# POWER.net
KiCad netlist of a schematic drawn in Altium Designer
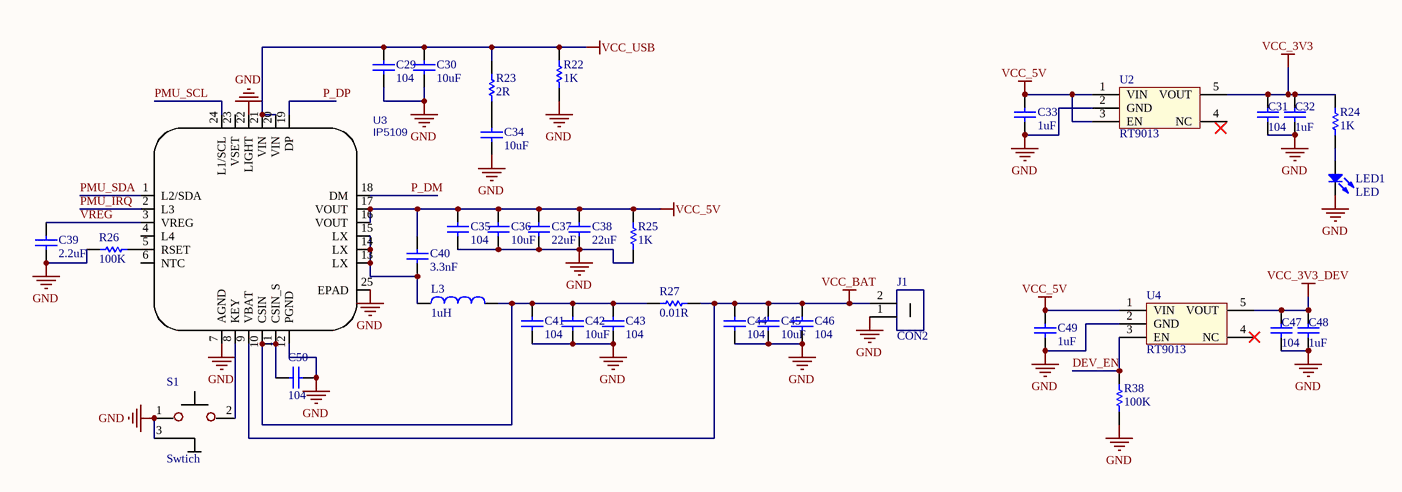
[diagram p0: POWER.SchDoc]

(export (version "E")
  (design (tool "Eeschema 10.0.6"))
  (components
    (comp (ref "C29")
      (value "104")
      (footprint "C 0603")
      (description "Capacitor")
      (libsource (lib "Miscellaneous Devices") (part "Cap"))
    )
    (comp (ref "C30")
      (value "10uF")
      (footprint "C 0603")
      (description "Capacitor")
      (libsource (lib "Miscellaneous Devices") (part "Cap"))
    )
    (comp (ref "C31") (value "104") (footprint "C 0603") (libsource (lib "Sheet") (part "CAP")))
    (comp (ref "C32") (value "1uF") (footprint "C 0603") (libsource (lib "Sheet") (part "CAP")))
    (comp (ref "C33") (value "1uF") (footprint "C 0603") (libsource (lib "Sheet") (part "CAP")))
    (comp (ref "C34")
      (value "10uF")
      (footprint "C 0603")
      (description "Capacitor")
      (libsource (lib "Miscellaneous Devices") (part "Cap"))
    )
    (comp (ref "C35")
      (value "104")
      (footprint "C 0603")
      (description "Capacitor")
      (libsource (lib "Miscellaneous Devices") (part "Cap"))
    )
    (comp (ref "C36")
      (value "10uF")
      (footprint "C 0603")
      (description "Capacitor")
      (libsource (lib "Miscellaneous Devices") (part "Cap"))
    )
    (comp (ref "C37")
      (value "22uF")
      (footprint "C 0603")
      (description "Capacitor")
      (libsource (lib "Miscellaneous Devices") (part "Cap"))
    )
    (comp (ref "C38")
      (value "22uF")
      (footprint "C 0603")
      (description "Capacitor")
      (libsource (lib "Miscellaneous Devices") (part "Cap"))
    )
    (comp (ref "C39") (value "2.2uF") (footprint "C 0603") (libsource (lib "Sheet") (part "CAP")))
    (comp (ref "C40")
      (value "3.3nF")
      (footprint "C 0603")
      (description "Capacitor")
      (libsource (lib "Miscellaneous Devices") (part "Cap"))
    )
    (comp (ref "C41")
      (value "104")
      (footprint "C 0603")
      (description "Capacitor")
      (libsource (lib "Miscellaneous Devices") (part "Cap"))
    )
    (comp (ref "C42")
      (value "10uF")
      (footprint "C 0603")
      (description "Capacitor")
      (libsource (lib "Miscellaneous Devices") (part "Cap"))
    )
    (comp (ref "C43")
      (value "104")
      (footprint "C 0603")
      (description "Capacitor")
      (libsource (lib "Miscellaneous Devices") (part "Cap"))
    )
    (comp (ref "C44")
      (value "104")
      (footprint "C 0603")
      (description "Capacitor")
      (libsource (lib "Miscellaneous Devices") (part "Cap"))
    )
    (comp (ref "C45")
      (value "10uF")
      (footprint "C 0603")
      (description "Capacitor")
      (libsource (lib "Miscellaneous Devices") (part "Cap"))
    )
    (comp (ref "C46")
      (value "104")
      (footprint "C 0603")
      (description "Capacitor")
      (libsource (lib "Miscellaneous Devices") (part "Cap"))
    )
    (comp (ref "C47") (value "104") (footprint "C 0603") (libsource (lib "Sheet") (part "CAP")))
    (comp (ref "C48") (value "1uF") (footprint "C 0603") (libsource (lib "Sheet") (part "CAP")))
    (comp (ref "C49") (value "1uF") (footprint "C 0603") (libsource (lib "Sheet") (part "CAP")))
    (comp (ref "C50")
      (value "104")
      (footprint "C 0603")
      (description "Capacitor")
      (libsource (lib "Miscellaneous Devices") (part "Cap"))
    )
    (comp (ref "J1") (value "CON2") (footprint "XH-2P-SMD") (libsource (lib "Sheet") (part "CON2")))
    (comp (ref "L3")
      (value "1uH")
      (footprint "L_7*7")
      (description "Inductor")
      (libsource (lib "Miscellaneous Devices") (part "Inductor"))
    )
    (comp (ref "LED1") (value "LED") (footprint "0603_LED") (libsource (lib "squ-guiboard") (part "LED")))
    (comp (ref "R22") (value "1K") (footprint "R 0603") (libsource (lib "Sheet") (part "RES")))
    (comp (ref "R23") (value "2R") (footprint "R 0603") (libsource (lib "Sheet") (part "RES")))
    (comp (ref "R24") (value "1K") (footprint "R 0603") (libsource (lib "Sheet") (part "RES")))
    (comp (ref "R25") (value "1K") (footprint "R 0603") (libsource (lib "Sheet") (part "RES")))
    (comp (ref "R26") (value "100K") (footprint "R 0603") (libsource (lib "Sheet") (part "RES")))
    (comp (ref "R27") (value "0.01R") (footprint "R 1206") (libsource (lib "Sheet") (part "RES")))
    (comp (ref "R38") (value "100K") (footprint "R 0603") (libsource (lib "Sheet") (part "RES")))
    (comp (ref "S1") (value "Swtich") (footprint "SW3*6") (libsource (lib "Sheet") (part "Switch-th")))
    (comp (ref "U2")
      (value "RT9013")
      (footprint "SOT23-5")
      (description "500mA低压差LDO")
      (libsource (lib "squ-guiboard") (part "RT9013"))
    )
    (comp (ref "U3")
      (value "IP5109")
      (footprint "QFN-24")
      (fields (field (name "BOM_SUPPLIER PART") "C181699") (field (name "CONTRIBUTOR") "LCSC"))
      (libsource (lib "Sheet") (part "IP5109"))
    )
    (comp (ref "U4")
      (value "RT9013")
      (footprint "SOT23-5")
      (description "500mA低压差LDO")
      (libsource (lib "squ-guiboard") (part "RT9013"))
    )
  )
  (nets
    (net (code "1") (name "/DEV_EN") (class "Default")
      (node (ref "R38") (pin "2") (pinfunction "2_2") (pintype "passive"))
      (node (ref "U4") (pin "3") (pinfunction "EN_3") (pintype "passive"))
    )
    (net (code "2") (name "/PMU_IRQ") (class "Default")
      (node (ref "U3") (pin "2") (pinfunction "L3_2") (pintype "passive"))
    )
    (net (code "3") (name "/PMU_SCL") (class "Default")
      (node (ref "U3") (pin "24") (pinfunction "L1/SCL_24") (pintype "passive"))
    )
    (net (code "4") (name "/PMU_SDA") (class "Default")
      (node (ref "U3") (pin "1") (pinfunction "L2/SDA_1") (pintype "passive"))
    )
    (net (code "5") (name "/P_DM") (class "Default")
      (node (ref "U3") (pin "18") (pinfunction "DM_18") (pintype "passive"))
    )
    (net (code "6") (name "/P_DP") (class "Default")
      (node (ref "U3") (pin "19") (pinfunction "DP_19") (pintype "passive"))
    )
    (net (code "7") (name "/VREG") (class "Default")
      (node (ref "C39") (pin "2") (pinfunction "2_2") (pintype "passive"))
      (node (ref "U3") (pin "3") (pinfunction "VREG_3") (pintype "passive"))
    )
    (net (code "8") (name "GND") (class "Default")
      (node (ref "C29") (pin "1") (pinfunction "1_1") (pintype "passive"))
      (node (ref "C30") (pin "1") (pinfunction "1_1") (pintype "passive"))
      (node (ref "C31") (pin "1") (pinfunction "1_1") (pintype "passive"))
      (node (ref "C32") (pin "1") (pinfunction "1_1") (pintype "passive"))
      (node (ref "C33") (pin "1") (pinfunction "1_1") (pintype "passive"))
      (node (ref "C34") (pin "1") (pinfunction "1_1") (pintype "passive"))
      (node (ref "C35") (pin "1") (pinfunction "1_1") (pintype "passive"))
      (node (ref "C36") (pin "1") (pinfunction "1_1") (pintype "passive"))
      (node (ref "C37") (pin "1") (pinfunction "1_1") (pintype "passive"))
      (node (ref "C38") (pin "1") (pinfunction "1_1") (pintype "passive"))
      (node (ref "C39") (pin "1") (pinfunction "1_1") (pintype "passive"))
      (node (ref "C41") (pin "1") (pinfunction "1_1") (pintype "passive"))
      (node (ref "C42") (pin "1") (pinfunction "1_1") (pintype "passive"))
      (node (ref "C43") (pin "1") (pinfunction "1_1") (pintype "passive"))
      (node (ref "C44") (pin "1") (pinfunction "1_1") (pintype "passive"))
      (node (ref "C45") (pin "1") (pinfunction "1_1") (pintype "passive"))
      (node (ref "C46") (pin "1") (pinfunction "1_1") (pintype "passive"))
      (node (ref "C47") (pin "1") (pinfunction "1_1") (pintype "passive"))
      (node (ref "C48") (pin "1") (pinfunction "1_1") (pintype "passive"))
      (node (ref "C49") (pin "1") (pinfunction "1_1") (pintype "passive"))
      (node (ref "C50") (pin "1") (pinfunction "1_1") (pintype "passive"))
      (node (ref "J1") (pin "1") (pinfunction "1_1") (pintype "passive"))
      (node (ref "LED1") (pin "2") (pinfunction "K_2") (pintype "passive"))
      (node (ref "R22") (pin "1") (pinfunction "1_1") (pintype "passive"))
      (node (ref "R25") (pin "1") (pinfunction "1_1") (pintype "passive"))
      (node (ref "R26") (pin "2") (pinfunction "2_2") (pintype "passive"))
      (node (ref "R38") (pin "1") (pinfunction "1_1") (pintype "passive"))
      (node (ref "S1") (pin "1") (pinfunction "1_1") (pintype "passive"))
      (node (ref "S1") (pin "3") (pinfunction "3_3") (pintype "passive"))
      (node (ref "U2") (pin "2") (pinfunction "GND_2") (pintype "passive"))
      (node (ref "U3") (pin "12") (pinfunction "PGND_12") (pintype "passive"))
      (node (ref "U3") (pin "22") (pinfunction "LIGHT_22") (pintype "passive"))
      (node (ref "U3") (pin "25") (pinfunction "EPAD_25") (pintype "passive"))
      (node (ref "U3") (pin "7") (pinfunction "AGND_7") (pintype "passive"))
      (node (ref "U4") (pin "2") (pinfunction "GND_2") (pintype "passive"))
    )
    (net (code "9") (name "Net-(C34-Pad2)") (class "Default")
      (node (ref "C34") (pin "2") (pinfunction "2_2") (pintype "passive"))
      (node (ref "R23") (pin "1") (pinfunction "1_1") (pintype "passive"))
    )
    (net (code "10") (name "Net-(C40-Pad1)") (class "Default")
      (node (ref "C40") (pin "1") (pinfunction "1_1") (pintype "passive"))
      (node (ref "L3") (pin "1") (pinfunction "1_1") (pintype "passive"))
      (node (ref "U3") (pin "13") (pinfunction "LX_13") (pintype "passive"))
      (node (ref "U3") (pin "14") (pinfunction "LX_14") (pintype "passive"))
      (node (ref "U3") (pin "15") (pinfunction "LX_15") (pintype "passive"))
    )
    (net (code "11") (name "Net-(LED1-A)") (class "Default")
      (node (ref "LED1") (pin "1") (pinfunction "A_1") (pintype "passive"))
      (node (ref "R24") (pin "1") (pinfunction "1_1") (pintype "passive"))
    )
    (net (code "12") (name "Net-(U3-CSIN)") (class "Default")
      (node (ref "C41") (pin "2") (pinfunction "2_2") (pintype "passive"))
      (node (ref "C42") (pin "2") (pinfunction "2_2") (pintype "passive"))
      (node (ref "C43") (pin "2") (pinfunction "2_2") (pintype "passive"))
      (node (ref "C50") (pin "2") (pinfunction "2_2") (pintype "passive"))
      (node (ref "L3") (pin "2") (pinfunction "2_2") (pintype "passive"))
      (node (ref "R27") (pin "2") (pinfunction "2_2") (pintype "passive"))
      (node (ref "U3") (pin "10") (pinfunction "CSIN_10") (pintype "passive"))
      (node (ref "U3") (pin "11") (pinfunction "CSIN_S_11") (pintype "passive"))
    )
    (net (code "13") (name "Net-(U3-KEY)") (class "Default")
      (node (ref "S1") (pin "2") (pinfunction "2_2") (pintype "passive"))
      (node (ref "U3") (pin "8") (pinfunction "KEY_8") (pintype "passive"))
    )
    (net (code "14") (name "Net-(U3-RSET)") (class "Default")
      (node (ref "R26") (pin "1") (pinfunction "1_1") (pintype "passive"))
      (node (ref "U3") (pin "5") (pinfunction "RSET_5") (pintype "passive"))
    )
    (net (code "15") (name "VCC_3V3") (class "Default")
      (node (ref "C31") (pin "2") (pinfunction "2_2") (pintype "passive"))
      (node (ref "C32") (pin "2") (pinfunction "2_2") (pintype "passive"))
      (node (ref "R24") (pin "2") (pinfunction "2_2") (pintype "passive"))
      (node (ref "U2") (pin "5") (pinfunction "VOUT_5") (pintype "passive"))
    )
    (net (code "16") (name "VCC_3V3_DEV") (class "Default")
      (node (ref "C47") (pin "2") (pinfunction "2_2") (pintype "passive"))
      (node (ref "C48") (pin "2") (pinfunction "2_2") (pintype "passive"))
      (node (ref "U4") (pin "5") (pinfunction "VOUT_5") (pintype "passive"))
    )
    (net (code "17") (name "VCC_5V") (class "Default")
      (node (ref "C33") (pin "2") (pinfunction "2_2") (pintype "passive"))
      (node (ref "C35") (pin "2") (pinfunction "2_2") (pintype "passive"))
      (node (ref "C36") (pin "2") (pinfunction "2_2") (pintype "passive"))
      (node (ref "C37") (pin "2") (pinfunction "2_2") (pintype "passive"))
      (node (ref "C38") (pin "2") (pinfunction "2_2") (pintype "passive"))
      (node (ref "C40") (pin "2") (pinfunction "2_2") (pintype "passive"))
      (node (ref "C49") (pin "2") (pinfunction "2_2") (pintype "passive"))
      (node (ref "R25") (pin "2") (pinfunction "2_2") (pintype "passive"))
      (node (ref "U2") (pin "1") (pinfunction "VIN_1") (pintype "passive"))
      (node (ref "U2") (pin "3") (pinfunction "EN_3") (pintype "passive"))
      (node (ref "U3") (pin "16") (pinfunction "VOUT_16") (pintype "passive"))
      (node (ref "U3") (pin "17") (pinfunction "VOUT_17") (pintype "passive"))
      (node (ref "U4") (pin "1") (pinfunction "VIN_1") (pintype "passive"))
    )
    (net (code "18") (name "VCC_BAT") (class "Default")
      (node (ref "C44") (pin "2") (pinfunction "2_2") (pintype "passive"))
      (node (ref "C45") (pin "2") (pinfunction "2_2") (pintype "passive"))
      (node (ref "C46") (pin "2") (pinfunction "2_2") (pintype "passive"))
      (node (ref "J1") (pin "2") (pinfunction "2_2") (pintype "passive"))
      (node (ref "R27") (pin "1") (pinfunction "1_1") (pintype "passive"))
      (node (ref "U3") (pin "9") (pinfunction "VBAT_9") (pintype "passive"))
    )
    (net (code "19") (name "VCC_USB") (class "Default")
      (node (ref "C29") (pin "2") (pinfunction "2_2") (pintype "passive"))
      (node (ref "C30") (pin "2") (pinfunction "2_2") (pintype "passive"))
      (node (ref "R22") (pin "2") (pinfunction "2_2") (pintype "passive"))
      (node (ref "R23") (pin "2") (pinfunction "2_2") (pintype "passive"))
      (node (ref "U3") (pin "20") (pinfunction "VIN_20") (pintype "passive"))
      (node (ref "U3") (pin "21") (pinfunction "VIN_21") (pintype "passive"))
    )
    (net (code "20") (name "unconnected-(U2-NC-Pad4)") (class "Default")
      (node (ref "U2") (pin "4") (pinfunction "NC_4") (pintype "passive"))
    )
    (net (code "21") (name "unconnected-(U3-L4-Pad4)") (class "Default")
      (node (ref "U3") (pin "4") (pinfunction "L4_4") (pintype "passive"))
    )
    (net (code "22") (name "unconnected-(U3-NTC-Pad6)") (class "Default")
      (node (ref "U3") (pin "6") (pinfunction "NTC_6") (pintype "passive"))
    )
    (net (code "23") (name "unconnected-(U3-VSET-Pad23)") (class "Default")
      (node (ref "U3") (pin "23") (pinfunction "VSET_23") (pintype "passive"))
    )
    (net (code "24") (name "unconnected-(U4-NC-Pad4)") (class "Default")
      (node (ref "U4") (pin "4") (pinfunction "NC_4") (pintype "passive+no_connect"))
    )
  )
)
